# WINGS_SIGNAL_SCH.net
KiCad netlist of a schematic drawn in Altium Designer
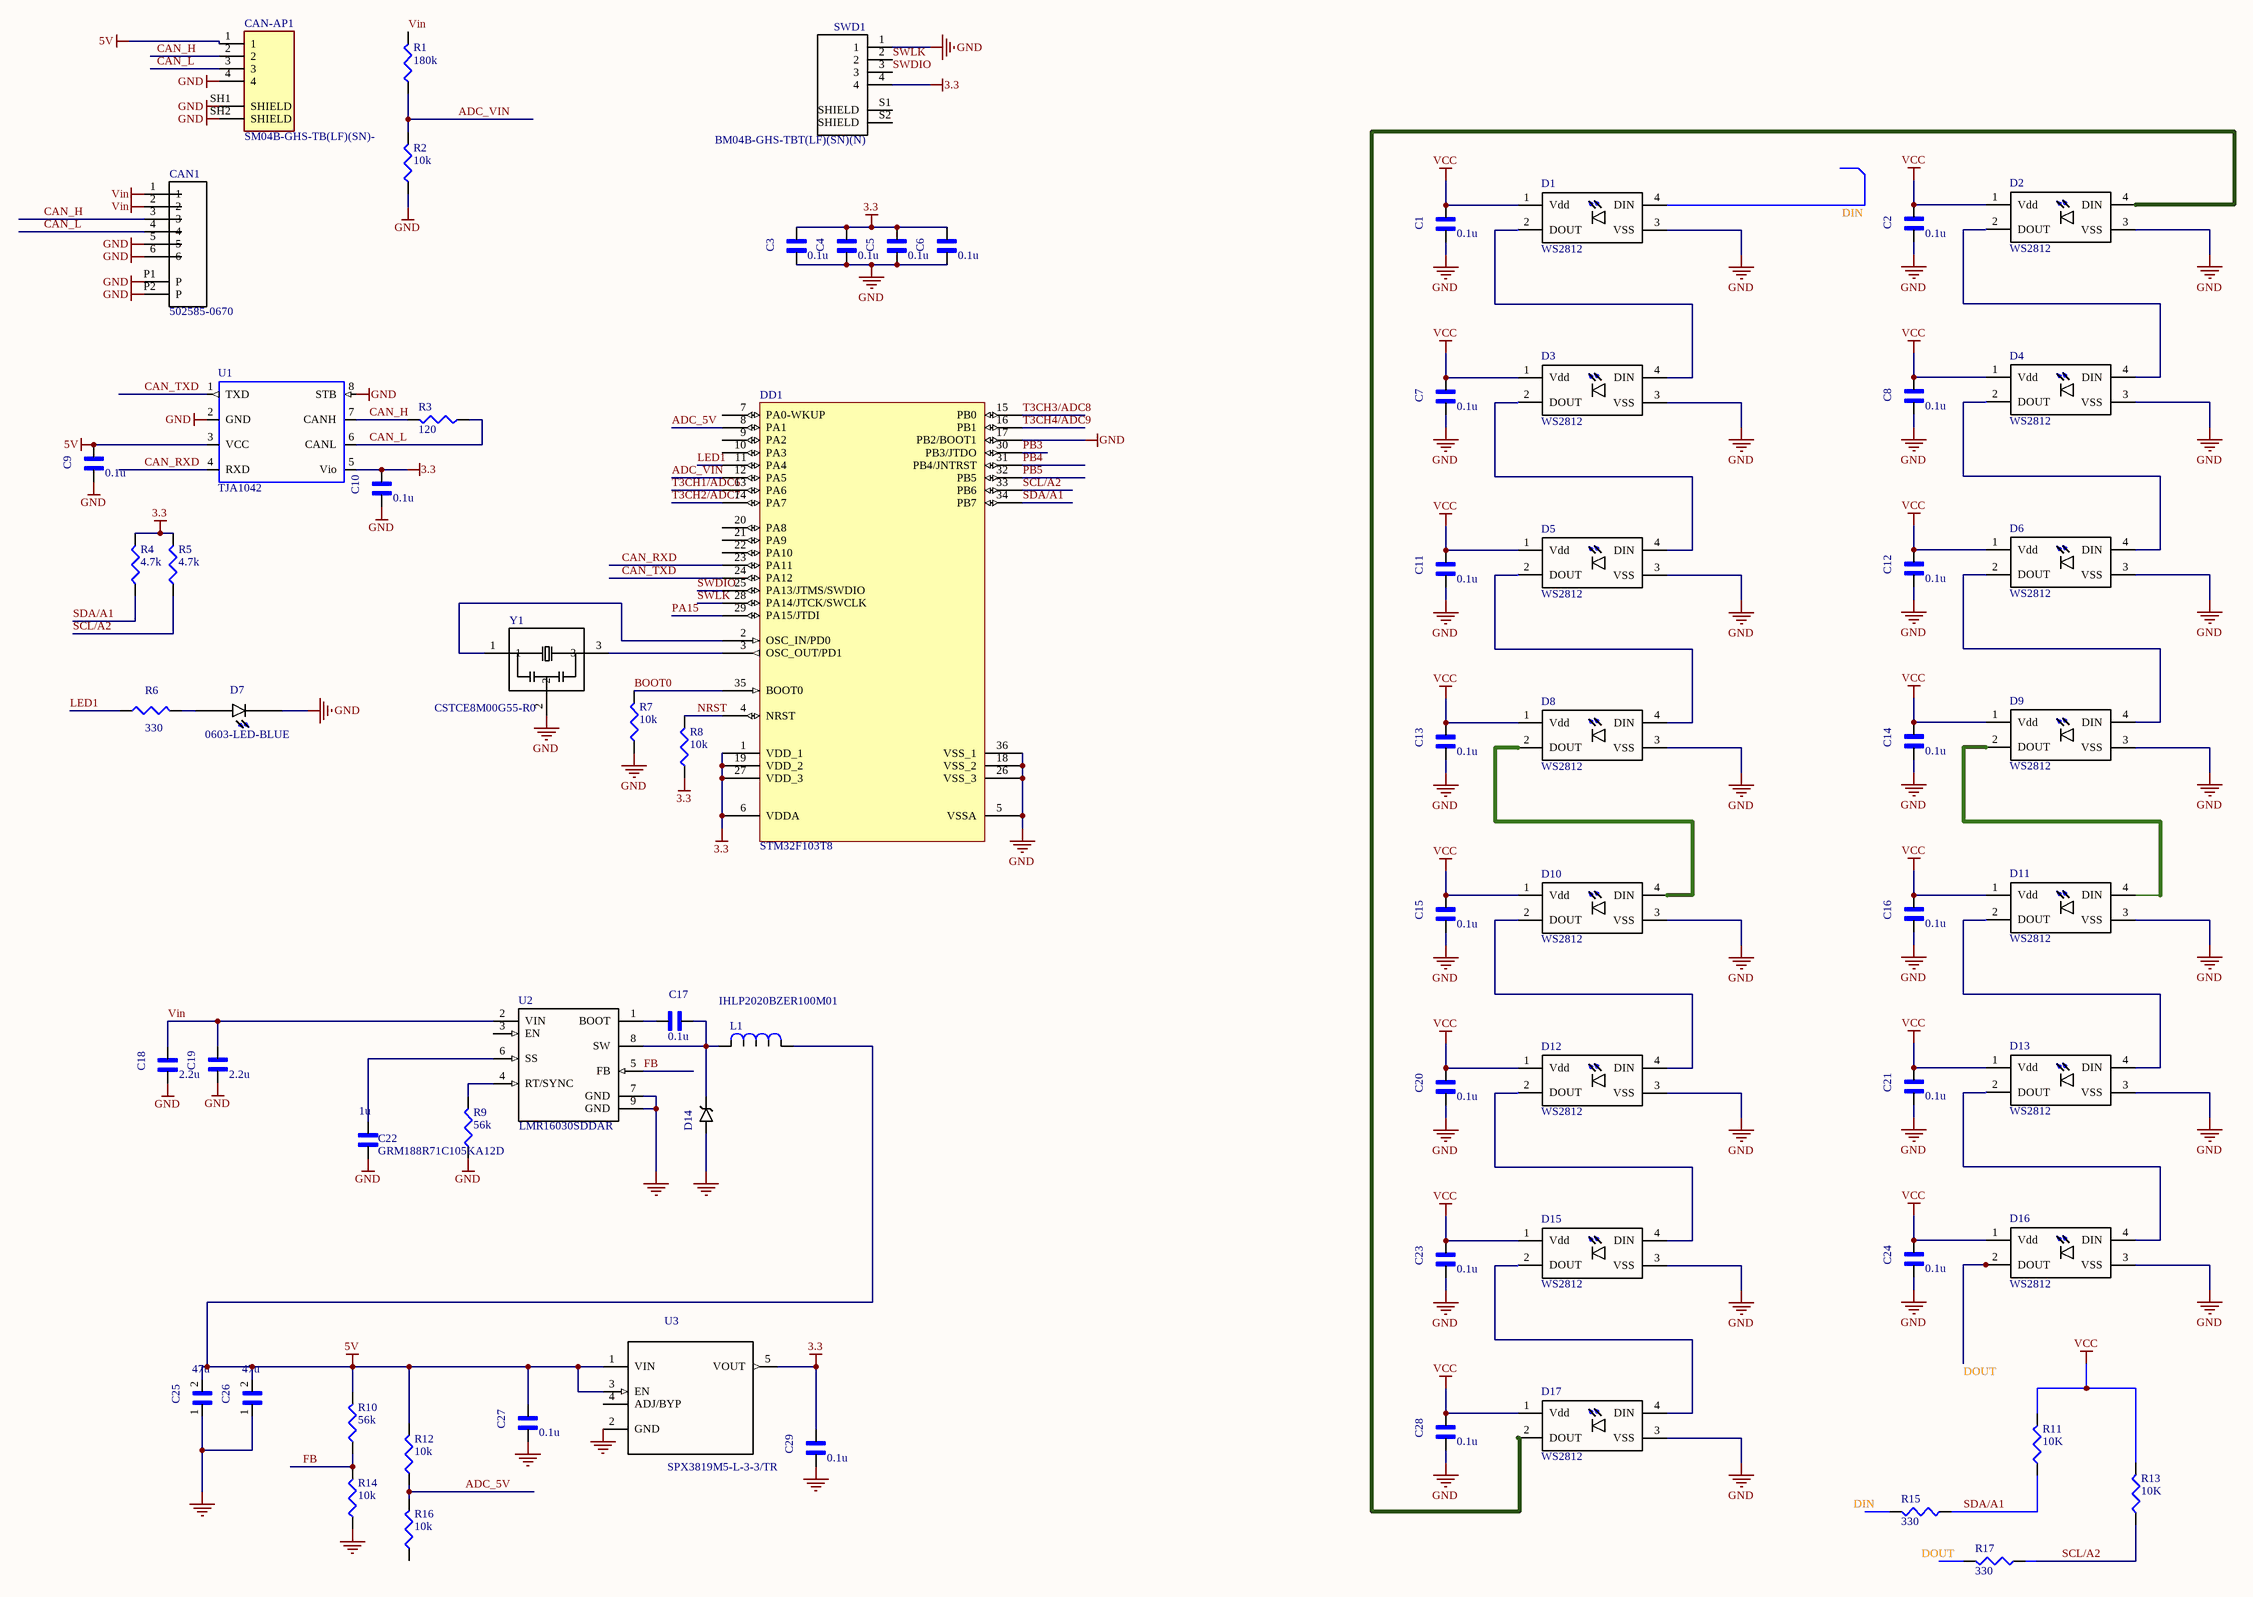
[diagram p0: WINGS_SIGNAL_SCH.SchDoc]

(export (version "E")
  (design (tool "Eeschema 10.0.6"))
  (components
    (comp (ref "C1")
      (value "0.1u")
      (footprint "*CAPC1608X90")
      (description "Cap Thin Film 0.1uf 50v 0603")
      (fields (field (name "MF") "AVX") (field (name "MP") "GX035C104MAT2-500 or CL10B104JB8NNNC"))
      (libsource (lib "lib") (part "GX035C104MAT2-500"))
    )
    (comp (ref "C2")
      (value "0.1u")
      (footprint "*CAPC1608X90")
      (description "Cap Thin Film 0.1uf 50v 0603")
      (fields (field (name "MF") "AVX") (field (name "MP") "GX035C104MAT2-500 or CL10B104JB8NNNC"))
      (libsource (lib "lib") (part "GX035C104MAT2-500"))
    )
    (comp (ref "C3")
      (value "0.1u")
      (footprint "*CAPC1608X90")
      (description "Cap Thin Film 0.1uf 50v 0603")
      (fields (field (name "MF") "AVX") (field (name "MP") "GX035C104MAT2-500 or CL10B104JB8NNNC"))
      (libsource (lib "lib") (part "GX035C104MAT2-500"))
    )
    (comp (ref "C4")
      (value "0.1u")
      (footprint "*CAPC1608X90")
      (description "Cap Thin Film 0.1uf 50v 0603")
      (fields (field (name "MF") "AVX") (field (name "MP") "GX035C104MAT2-500 or CL10B104JB8NNNC"))
      (libsource (lib "lib") (part "GX035C104MAT2-500"))
    )
    (comp (ref "C5")
      (value "0.1u")
      (footprint "*CAPC1608X90")
      (description "Cap Thin Film 0.1uf 50v 0603")
      (fields (field (name "MF") "AVX") (field (name "MP") "GX035C104MAT2-500 or CL10B104JB8NNNC"))
      (libsource (lib "lib") (part "GX035C104MAT2-500"))
    )
    (comp (ref "C6")
      (value "0.1u")
      (footprint "*CAPC1608X90")
      (description "Cap Thin Film 0.1uf 50v 0603")
      (fields (field (name "MF") "AVX") (field (name "MP") "GX035C104MAT2-500 or CL10B104JB8NNNC"))
      (libsource (lib "lib") (part "GX035C104MAT2-500"))
    )
    (comp (ref "C7")
      (value "0.1u")
      (footprint "*CAPC1608X90")
      (description "Cap Thin Film 0.1uf 50v 0603")
      (fields (field (name "MF") "AVX") (field (name "MP") "GX035C104MAT2-500 or CL10B104JB8NNNC"))
      (libsource (lib "lib") (part "GX035C104MAT2-500"))
    )
    (comp (ref "C8")
      (value "0.1u")
      (footprint "*CAPC1608X90")
      (description "Cap Thin Film 0.1uf 50v 0603")
      (fields (field (name "MF") "AVX") (field (name "MP") "GX035C104MAT2-500 or CL10B104JB8NNNC"))
      (libsource (lib "lib") (part "GX035C104MAT2-500"))
    )
    (comp (ref "C9")
      (value "0.1u")
      (footprint "*CAPC1608X90")
      (description "Cap Thin Film 0.1uf 50v 0603")
      (fields (field (name "MF") "AVX") (field (name "MP") "GX035C104MAT2-500 or CL10B104JB8NNNC"))
      (libsource (lib "lib") (part "GX035C104MAT2-500"))
    )
    (comp (ref "C10")
      (value "0.1u")
      (footprint "*CAPC1608X90")
      (description "Cap Thin Film 0.1uf 50v 0603")
      (fields (field (name "MF") "AVX") (field (name "MP") "GX035C104MAT2-500 or CL10B104JB8NNNC"))
      (libsource (lib "lib") (part "GX035C104MAT2-500"))
    )
    (comp (ref "C11")
      (value "0.1u")
      (footprint "*CAPC1608X90")
      (description "Cap Thin Film 0.1uf 50v 0603")
      (fields (field (name "MF") "AVX") (field (name "MP") "GX035C104MAT2-500 or CL10B104JB8NNNC"))
      (libsource (lib "lib") (part "GX035C104MAT2-500"))
    )
    (comp (ref "C12")
      (value "0.1u")
      (footprint "*CAPC1608X90")
      (description "Cap Thin Film 0.1uf 50v 0603")
      (fields (field (name "MF") "AVX") (field (name "MP") "GX035C104MAT2-500 or CL10B104JB8NNNC"))
      (libsource (lib "lib") (part "GX035C104MAT2-500"))
    )
    (comp (ref "C13")
      (value "0.1u")
      (footprint "*CAPC1608X90")
      (description "Cap Thin Film 0.1uf 50v 0603")
      (fields (field (name "MF") "AVX") (field (name "MP") "GX035C104MAT2-500 or CL10B104JB8NNNC"))
      (libsource (lib "lib") (part "GX035C104MAT2-500"))
    )
    (comp (ref "C14")
      (value "0.1u")
      (footprint "*CAPC1608X90")
      (description "Cap Thin Film 0.1uf 50v 0603")
      (fields (field (name "MF") "AVX") (field (name "MP") "GX035C104MAT2-500 or CL10B104JB8NNNC"))
      (libsource (lib "lib") (part "GX035C104MAT2-500"))
    )
    (comp (ref "C15")
      (value "0.1u")
      (footprint "*CAPC1608X90")
      (description "Cap Thin Film 0.1uf 50v 0603")
      (fields (field (name "MF") "AVX") (field (name "MP") "GX035C104MAT2-500 or CL10B104JB8NNNC"))
      (libsource (lib "lib") (part "GX035C104MAT2-500"))
    )
    (comp (ref "C16")
      (value "0.1u")
      (footprint "*CAPC1608X90")
      (description "Cap Thin Film 0.1uf 50v 0603")
      (fields (field (name "MF") "AVX") (field (name "MP") "GX035C104MAT2-500 or CL10B104JB8NNNC"))
      (libsource (lib "lib") (part "GX035C104MAT2-500"))
    )
    (comp (ref "C17")
      (value "0.1u")
      (footprint "*CAPC1608X90")
      (description "Cap Thin Film 0.1uf 50v 0603")
      (fields (field (name "MF") "AVX") (field (name "MP") "GX035C104MAT2-500 or CL10B104JB8NNNC"))
      (libsource (lib "lib") (part "GX035C104MAT2-500"))
    )
    (comp (ref "C18")
      (value "2.2u")
      (footprint "*CAP3216X125N")
      (description "1206 2.2 uF 50 V В±10% Tolerance X7R SMT Multilayer Ceramic Capacitor")
      (fields (field (name "MF") "Murata Electronics") (field (name "MP") "GRM31CR71H225KA88L"))
      (libsource (lib "lib") (part "GRM31CR71H225KA88L"))
    )
    (comp (ref "C19")
      (value "2.2u")
      (footprint "*CAP3216X125N")
      (description "1206 2.2 uF 50 V В±10% Tolerance X7R SMT Multilayer Ceramic Capacitor")
      (fields (field (name "MF") "Murata Electronics") (field (name "MP") "GRM31CR71H225KA88L"))
      (libsource (lib "lib") (part "GRM31CR71H225KA88L"))
    )
    (comp (ref "C20")
      (value "0.1u")
      (footprint "*CAPC1608X90")
      (description "Cap Thin Film 0.1uf 50v 0603")
      (fields (field (name "MF") "AVX") (field (name "MP") "GX035C104MAT2-500 or CL10B104JB8NNNC"))
      (libsource (lib "lib") (part "GX035C104MAT2-500"))
    )
    (comp (ref "C21")
      (value "0.1u")
      (footprint "*CAPC1608X90")
      (description "Cap Thin Film 0.1uf 50v 0603")
      (fields (field (name "MF") "AVX") (field (name "MP") "GX035C104MAT2-500 or CL10B104JB8NNNC"))
      (libsource (lib "lib") (part "GX035C104MAT2-500"))
    )
    (comp (ref "C22")
      (value "GRM188R71C105KA12D")
      (footprint "CAPC1608X90N")
      (description "SMD Capacitor X7R(EIA) with Capacitance: 1.0uF Tol. 10%. Rated Voltage: 16Vdc")
      (fields (field (name "MF") "Murata Electronics") (field (name "ALTIUM_VALUE") "1u"))
      (libsource (lib "lib") (part "GRM188R71C105KA12D"))
    )
    (comp (ref "C23")
      (value "0.1u")
      (footprint "*CAPC1608X90")
      (description "Cap Thin Film 0.1uf 50v 0603")
      (fields (field (name "MF") "AVX") (field (name "MP") "GX035C104MAT2-500 or CL10B104JB8NNNC"))
      (libsource (lib "lib") (part "GX035C104MAT2-500"))
    )
    (comp (ref "C24")
      (value "0.1u")
      (footprint "*CAPC1608X90")
      (description "Cap Thin Film 0.1uf 50v 0603")
      (fields (field (name "MF") "AVX") (field (name "MP") "GX035C104MAT2-500 or CL10B104JB8NNNC"))
      (libsource (lib "lib") (part "GX035C104MAT2-500"))
    )
    (comp (ref "C25")
      (value "47u")
      (footprint "*CAPC3216X125N")
      (description "Multilayer Ceramic Capacitor, GRM Series, 47 - F, - 10%, X5R, 10 V, 1206 [3216 Metric]")
      (fields (field (name "MF") "Murata Electronics") (field (name "MP") "GRM31CR61A476KE15L"))
      (libsource (lib "lib") (part "GRM31CR61A476KE15L"))
    )
    (comp (ref "C26")
      (value "47u")
      (footprint "*CAPC3216X125N")
      (description "Multilayer Ceramic Capacitor, GRM Series, 47 - F, - 10%, X5R, 10 V, 1206 [3216 Metric]")
      (fields (field (name "MF") "Murata Electronics") (field (name "MP") "GRM31CR61A476KE15L"))
      (libsource (lib "lib") (part "GRM31CR61A476KE15L"))
    )
    (comp (ref "C27")
      (value "0.1u")
      (footprint "*CAPC1608X90")
      (description "Cap Thin Film 0.1uf 50v 0603")
      (fields (field (name "MF") "AVX") (field (name "MP") "GX035C104MAT2-500"))
      (libsource (lib "lib") (part "GX035C104MAT2-500"))
    )
    (comp (ref "C28")
      (value "0.1u")
      (footprint "*CAPC1608X90")
      (description "Cap Thin Film 0.1uf 50v 0603")
      (fields (field (name "MF") "AVX") (field (name "MP") "GX035C104MAT2-500 or CL10B104JB8NNNC"))
      (libsource (lib "lib") (part "GX035C104MAT2-500"))
    )
    (comp (ref "C29")
      (value "0.1u")
      (footprint "*CAPC1608X90")
      (description "Cap Thin Film 0.1uf 50v 0603")
      (fields (field (name "MF") "AVX") (field (name "MP") "GX035C104MAT2-500"))
      (libsource (lib "lib") (part "GX035C104MAT2-500"))
    )
    (comp (ref "CAN-AP1")
      (value "SM04B-GHS-TB(LF)(SN)-")
      (footprint "JST_SM04B-GHS-TB(LF)(SN)-")
      (description "Connector Header Surface Mount, Right Angle 4 position 0.049 _1.25mm_")
      (fields (field (name "MP") "SM04B-GHS-TB(LF)(SN)") (field (name "MF") "JST Sales"))
      (libsource (lib "lib") (part "SM04B-GHS-TB(LF)(SN)-"))
    )
    (comp (ref "CAN1")
      (value "502585-0670")
      (footprint "MOLEX_502585-0670")
      (fields (field (name "MF") "Molex"))
      (libsource (lib "lib") (part "502585-0670"))
    )
    (comp (ref "D1")
      (value "WS2812")
      (footprint "LED_WS2812")
      (description "Addressable Lighting - 5 LED Discrete Serial _Shift Register_ Red, Green, Blue _RGB_ 5.00mm Dia")
      (fields (field (name "MF") "SparkFun Electronics"))
      (libsource (lib "lib") (part "WS2812"))
    )
    (comp (ref "D2")
      (value "WS2812")
      (footprint "LED_WS2812")
      (description "Addressable Lighting - 5 LED Discrete Serial _Shift Register_ Red, Green, Blue _RGB_ 5.00mm Dia")
      (fields (field (name "MF") "SparkFun Electronics"))
      (libsource (lib "lib") (part "WS2812"))
    )
    (comp (ref "D3")
      (value "WS2812")
      (footprint "LED_WS2812")
      (description "Addressable Lighting - 5 LED Discrete Serial _Shift Register_ Red, Green, Blue _RGB_ 5.00mm Dia")
      (fields (field (name "MF") "SparkFun Electronics"))
      (libsource (lib "lib") (part "WS2812"))
    )
    (comp (ref "D4")
      (value "WS2812")
      (footprint "LED_WS2812")
      (description "Addressable Lighting - 5 LED Discrete Serial _Shift Register_ Red, Green, Blue _RGB_ 5.00mm Dia")
      (fields (field (name "MF") "SparkFun Electronics"))
      (libsource (lib "lib") (part "WS2812"))
    )
    (comp (ref "D5")
      (value "WS2812")
      (footprint "LED_WS2812")
      (description "Addressable Lighting - 5 LED Discrete Serial _Shift Register_ Red, Green, Blue _RGB_ 5.00mm Dia")
      (fields (field (name "MF") "SparkFun Electronics"))
      (libsource (lib "lib") (part "WS2812"))
    )
    (comp (ref "D6")
      (value "WS2812")
      (footprint "LED_WS2812")
      (description "Addressable Lighting - 5 LED Discrete Serial _Shift Register_ Red, Green, Blue _RGB_ 5.00mm Dia")
      (fields (field (name "MF") "SparkFun Electronics"))
      (libsource (lib "lib") (part "WS2812"))
    )
    (comp (ref "D7")
      (value "0603-LED-BLUE")
      (footprint "*LEDM1608X80_LTE-C1906R-14(Primary)")
      (description "LED IrLED Chip LED 2-Pin SMD T/R")
      (libsource (lib "lib") (part "LTE-C1906R-14"))
    )
    (comp (ref "D8")
      (value "WS2812")
      (footprint "LED_WS2812")
      (description "Addressable Lighting - 5 LED Discrete Serial _Shift Register_ Red, Green, Blue _RGB_ 5.00mm Dia")
      (fields (field (name "MF") "SparkFun Electronics"))
      (libsource (lib "lib") (part "WS2812"))
    )
    (comp (ref "D9")
      (value "WS2812")
      (footprint "LED_WS2812")
      (description "Addressable Lighting - 5 LED Discrete Serial _Shift Register_ Red, Green, Blue _RGB_ 5.00mm Dia")
      (fields (field (name "MF") "SparkFun Electronics"))
      (libsource (lib "lib") (part "WS2812"))
    )
    (comp (ref "D10")
      (value "WS2812")
      (footprint "LED_WS2812")
      (description "Addressable Lighting - 5 LED Discrete Serial _Shift Register_ Red, Green, Blue _RGB_ 5.00mm Dia")
      (fields (field (name "MF") "SparkFun Electronics"))
      (libsource (lib "lib") (part "WS2812"))
    )
    (comp (ref "D11")
      (value "WS2812")
      (footprint "LED_WS2812")
      (description "Addressable Lighting - 5 LED Discrete Serial _Shift Register_ Red, Green, Blue _RGB_ 5.00mm Dia")
      (fields (field (name "MF") "SparkFun Electronics"))
      (libsource (lib "lib") (part "WS2812"))
    )
    (comp (ref "D12")
      (value "WS2812")
      (footprint "LED_WS2812")
      (description "Addressable Lighting - 5 LED Discrete Serial _Shift Register_ Red, Green, Blue _RGB_ 5.00mm Dia")
      (fields (field (name "MF") "SparkFun Electronics"))
      (libsource (lib "lib") (part "WS2812"))
    )
    (comp (ref "D13")
      (value "WS2812")
      (footprint "LED_WS2812")
      (description "Addressable Lighting - 5 LED Discrete Serial _Shift Register_ Red, Green, Blue _RGB_ 5.00mm Dia")
      (fields (field (name "MF") "SparkFun Electronics"))
      (libsource (lib "lib") (part "WS2812"))
    )
    (comp (ref "D14")
      (value "SK56")
      (footprint "*SMB_P6SMB62AT3G(Primary)")
      (description "Диод Шоттки 5А 60В [SMB / DO-214AA]")
      (fields (field (name "MF") "Littelfuse Inc."))
      (libsource (lib "lib") (part "SK56"))
    )
    (comp (ref "D15")
      (value "WS2812")
      (footprint "LED_WS2812")
      (description "Addressable Lighting - 5 LED Discrete Serial _Shift Register_ Red, Green, Blue _RGB_ 5.00mm Dia")
      (fields (field (name "MF") "SparkFun Electronics"))
      (libsource (lib "lib") (part "WS2812"))
    )
    (comp (ref "D16")
      (value "WS2812")
      (footprint "LED_WS2812")
      (description "Addressable Lighting - 5 LED Discrete Serial _Shift Register_ Red, Green, Blue _RGB_ 5.00mm Dia")
      (fields (field (name "MF") "SparkFun Electronics"))
      (libsource (lib "lib") (part "WS2812"))
    )
    (comp (ref "D17")
      (value "WS2812")
      (footprint "LED_WS2812")
      (description "Addressable Lighting - 5 LED Discrete Serial _Shift Register_ Red, Green, Blue _RGB_ 5.00mm Dia")
      (fields (field (name "MF") "SparkFun Electronics"))
      (libsource (lib "lib") (part "WS2812"))
    )
    (comp (ref "DD1")
      (value "STM32F103T8")
      (footprint "*QFN50P600X600X100-37N")
      (description "STM32F103T8U6, Микроконтроллер 32BIT ARM 64K FLASH [VFQFPN-36]")
      (fields (field (name "MF") "STM") (field (name "MP") "STM32F103T8U6"))
      (libsource (lib "lib") (part "STM32F103T8"))
    )
    (comp (ref "L1")
      (value "IHLP2020BZER100M01")
      (footprint "IHLP")
      (description "10ÂµH Shielded Molded Inductor 2.3A 199mOhm Max Nonstandard")
      (fields (field (name "MF") "Vishay Dale"))
      (libsource (lib "lib") (part "IHLP2020BZER100M01"))
    )
    (comp (ref "R1")
      (value "180k")
      (footprint "J1-0603")
      (description "Resistor")
      (fields (field (name "MP") "180K 1% 0603") (field (name "Comment") "Res3"))
      (libsource (lib "Miscellaneous Devices") (part "Res3"))
    )
    (comp (ref "R2")
      (value "10k")
      (footprint "J1-0603")
      (description "Resistor")
      (fields (field (name "MP") "10K 1% 0603") (field (name "Comment") "Res3"))
      (libsource (lib "Miscellaneous Devices") (part "Res3"))
    )
    (comp (ref "R3")
      (value "120")
      (footprint "J1-0603")
      (description "120 Ohms 1 0.1 W 1 10 W Chip Resistor 0603 1608 Metric Thick Film")
      (fields (field (name "MP") "RC0603FR-07120RL") (field (name "Comment") "Res3"))
      (libsource (lib "Miscellaneous Devices") (part "Res3"))
    )
    (comp (ref "R4")
      (value "4.7k")
      (footprint "J1-0603")
      (description "Resistor")
      (fields (field (name "MP") "4.7K 1% 0603") (field (name "Comment") "Res3"))
      (libsource (lib "Miscellaneous Devices") (part "Res3"))
    )
    (comp (ref "R5")
      (value "4.7k")
      (footprint "J1-0603")
      (description "Resistor")
      (fields (field (name "MP") "4.7K 1% 0603") (field (name "Comment") "Res3"))
      (libsource (lib "Miscellaneous Devices") (part "Res3"))
    )
    (comp (ref "R6")
      (value "330")
      (footprint "J1-0603")
      (description "Resistor")
      (fields (field (name "MP") "RC0603FR-07330RL") (field (name "Comment") "Res3"))
      (libsource (lib "Miscellaneous Devices") (part "Res3"))
    )
    (comp (ref "R7")
      (value "10k")
      (footprint "J1-0603")
      (description "10 kOhms 1 0.1 W 1 10 W Chip Resistor 0603 1608 Metric Thick Film")
      (fields (field (name "MF") "Yageo or NXP") (field (name "MP") "10K 1% 0603"))
      (libsource (lib "CAN_NODE_MINI") (part "RC0603FR-0710KL"))
    )
    (comp (ref "R8")
      (value "10k")
      (footprint "J1-0603")
      (description "10 kOhms 1 0.1 W 1 10 W Chip Resistor 0603 1608 Metric Thick Film")
      (fields (field (name "MF") "Yageo or NXP") (field (name "MP") "10K 1% 0603"))
      (libsource (lib "CAN_NODE_MINI") (part "RC0603FR-0710KL"))
    )
    (comp (ref "R9")
      (value "56k")
      (footprint "J1-0603")
      (description "Resistor")
      (fields (field (name "MP") "RC0603FR-0756KL") (field (name "Comment") "Res3"))
      (libsource (lib "Miscellaneous Devices") (part "Res3"))
    )
    (comp (ref "R10")
      (value "56k")
      (footprint "J1-0603")
      (description "Resistor")
      (fields (field (name "MP") "RC0603FR-0756KL") (field (name "Comment") "Res3"))
      (libsource (lib "Miscellaneous Devices") (part "Res3"))
    )
    (comp (ref "R11")
      (value "10K")
      (footprint "J1-0603")
      (description "Resistor")
      (fields (field (name "MP") "4.7K 1% 0603") (field (name "Comment") "Res3"))
      (libsource (lib "Miscellaneous Devices") (part "Res3"))
    )
    (comp (ref "R12")
      (value "10k")
      (footprint "J1-0603")
      (description "10 kOhms 1 0.1 W 1 10 W Chip Resistor 0603 1608 Metric Thick Film")
      (fields (field (name "MF") "Yageo or NXP") (field (name "MP") "10K 1% 0603"))
      (libsource (lib "CAN_NODE_MINI") (part "RC0603FR-0710KL"))
    )
    (comp (ref "R13")
      (value "10K")
      (footprint "J1-0603")
      (description "Resistor")
      (fields (field (name "MP") "4.7K 1% 0603") (field (name "Comment") "Res3"))
      (libsource (lib "Miscellaneous Devices") (part "Res3"))
    )
    (comp (ref "R14")
      (value "10k")
      (footprint "J1-0603")
      (description "10 kOhms 1 0.1 W 1 10 W Chip Resistor 0603 1608 Metric Thick Film")
      (fields (field (name "MF") "Yageo or NXP") (field (name "MP") "10K 1% 0603"))
      (libsource (lib "CAN_NODE_MINI") (part "RC0603FR-0710KL"))
    )
    (comp (ref "R15")
      (value "330")
      (footprint "J1-0603")
      (description "Resistor")
      (fields (field (name "MP") "4.7K 1% 0603") (field (name "Comment") "Res3"))
      (libsource (lib "Miscellaneous Devices") (part "Res3"))
    )
    (comp (ref "R16")
      (value "10k")
      (footprint "J1-0603")
      (description "10 kOhms 1 0.1 W 1 10 W Chip Resistor 0603 1608 Metric Thick Film")
      (fields (field (name "MF") "Yageo or NXP") (field (name "MP") "10K 1% 0603"))
      (libsource (lib "CAN_NODE_MINI") (part "RC0603FR-0710KL"))
    )
    (comp (ref "R17")
      (value "330")
      (footprint "J1-0603")
      (description "Resistor")
      (fields (field (name "MP") "4.7K 1% 0603") (field (name "Comment") "Res3"))
      (libsource (lib "Miscellaneous Devices") (part "Res3"))
    )
    (comp (ref "SWD1")
      (value "BM04B-GHS-TBT(LF)(SN)(N)")
      (footprint "JST_BM04B-GHS-holes")
      (description "Conn Shrouded Header HDR 4 POS 1.25mm Solder ST SMD Reel")
      (fields (field (name "MF") "JST Sales") (field (name "MP") "SM04B-GHS-TB(LF)(SN)"))
      (libsource (lib "lib") (part "BM04B-GHS-TBT(LF)(SN)(N)"))
    )
    (comp (ref "U1")
      (value "TJA1042")
      (footprint "SOT782-1")
      (description "1/1 Transceiver Half CANbus 8-SO")
      (fields (field (name "MF") "NXP USA"))
      (libsource (lib "lib") (part "TJA1042"))
    )
    (comp (ref "U2")
      (value "LMR16030SDDAR")
      (footprint "*SOIC127P600X170-9N - duplicate")
      (fields (field (name "MF") "Texas Instruments"))
      (libsource (lib "lib") (part "LMR16030SDDAR"))
    )
    (comp (ref "U3")
      (value "SPX3819M5-L-3-3/TR")
      (footprint "*SOT95P280X145-5N")
      (description "Low Dropout Voltage Regulator, Adjustable 0.5A, В±1%, 2.5 to 16 Vin, 5-Pin SOT-23")
      (fields (field (name "MF") "MaxLinear, Inc."))
      (libsource (lib "DC_DC") (part "SPX3819M5-L"))
    )
    (comp (ref "Y1")
      (value "CSTCE8M00G55-R0")
      (footprint "*OSC_CSTCE8M00G55-R0")
      (description "Ceramic Resonator 8MHz ??0.5% _Tol_ ??0.2% _Stability_ 33pF 40Ohm 3-Pin CSMD T/R")
      (fields (field (name "MF") "Murata"))
      (libsource (lib "DC_DC") (part "CSTCE8M00G55-R0"))
    )
  )
  (nets
    (net (code "1") (name "/ADC_5V") (class "Default")
      (node (ref "DD1") (pin "8") (pinfunction "PA1_8") (pintype "bidirectional"))
      (node (ref "R12") (pin "1") (pinfunction "1_1") (pintype "passive"))
      (node (ref "R16") (pin "2") (pinfunction "2_2") (pintype "passive"))
    )
    (net (code "2") (name "/ADC_VIN") (class "Default")
      (node (ref "DD1") (pin "12") (pinfunction "PA5_12") (pintype "bidirectional"))
      (node (ref "R1") (pin "1") (pinfunction "1_1") (pintype "passive"))
      (node (ref "R2") (pin "2") (pinfunction "2_2") (pintype "passive"))
    )
    (net (code "3") (name "/BOOT0") (class "Default")
      (node (ref "DD1") (pin "35") (pinfunction "BOOT0_35") (pintype "input"))
      (node (ref "R7") (pin "2") (pinfunction "2_2") (pintype "passive"))
    )
    (net (code "4") (name "/CAN_H") (class "Default")
      (node (ref "CAN-AP1") (pin "2") (pinfunction "2_2") (pintype "passive"))
      (node (ref "CAN1") (pin "3") (pinfunction "3_3") (pintype "passive"))
      (node (ref "R3") (pin "2") (pinfunction "2_2") (pintype "passive"))
      (node (ref "U1") (pin "7") (pinfunction "CANH_7") (pintype "bidirectional"))
    )
    (net (code "5") (name "/CAN_L") (class "Default")
      (node (ref "CAN-AP1") (pin "3") (pinfunction "3_3") (pintype "passive"))
      (node (ref "CAN1") (pin "4") (pinfunction "4_4") (pintype "passive"))
      (node (ref "R3") (pin "1") (pinfunction "1_1") (pintype "passive"))
      (node (ref "U1") (pin "6") (pinfunction "CANL_6") (pintype "bidirectional"))
    )
    (net (code "6") (name "/CAN_RXD") (class "Default")
      (node (ref "DD1") (pin "23") (pinfunction "PA11_23") (pintype "bidirectional"))
      (node (ref "U1") (pin "4") (pinfunction "RXD_4") (pintype "bidirectional"))
    )
    (net (code "7") (name "/CAN_TXD") (class "Default")
      (node (ref "DD1") (pin "24") (pinfunction "PA12_24") (pintype "bidirectional"))
      (node (ref "U1") (pin "1") (pinfunction "TXD_1") (pintype "output"))
    )
    (net (code "8") (name "/DIN") (class "Default")
      (node (ref "D1") (pin "4") (pinfunction "DIN_4") (pintype "power_in"))
      (node (ref "R15") (pin "2") (pinfunction "2_2") (pintype "passive"))
    )
    (net (code "9") (name "/DOUT") (class "Default")
      (node (ref "D16") (pin "2") (pinfunction "DOUT_2") (pintype "power_in"))
      (node (ref "R17") (pin "2") (pinfunction "2_2") (pintype "passive"))
    )
    (net (code "10") (name "/FB") (class "Default")
      (node (ref "R10") (pin "1") (pinfunction "1_1") (pintype "passive"))
      (node (ref "R14") (pin "2") (pinfunction "2_2") (pintype "passive"))
      (node (ref "U2") (pin "5") (pinfunction "FB_5") (pintype "input"))
    )
    (net (code "11") (name "/LED1") (class "Default")
      (node (ref "DD1") (pin "11") (pinfunction "PA4_11") (pintype "bidirectional"))
      (node (ref "R6") (pin "1") (pinfunction "1_1") (pintype "passive"))
    )
    (net (code "12") (name "/NRST") (class "Default")
      (node (ref "DD1") (pin "4") (pinfunction "NRST_4") (pintype "bidirectional"))
      (node (ref "R8") (pin "2") (pinfunction "2_2") (pintype "passive"))
    )
    (net (code "13") (name "/PA15") (class "Default")
      (node (ref "DD1") (pin "29") (pinfunction "PA15/JTDI_29") (pintype "bidirectional"))
    )
    (net (code "14") (name "/PB3") (class "Default")
      (node (ref "DD1") (pin "30") (pinfunction "PB3/JTDO_30") (pintype "bidirectional"))
    )
    (net (code "15") (name "/PB4") (class "Default")
      (node (ref "DD1") (pin "31") (pinfunction "PB4/JNTRST_31") (pintype "bidirectional"))
    )
    (net (code "16") (name "/PB5") (class "Default")
      (node (ref "DD1") (pin "32") (pinfunction "PB5_32") (pintype "bidirectional"))
    )
    (net (code "17") (name "/SCL{slash}A2") (class "Default")
      (node (ref "DD1") (pin "33") (pinfunction "PB6_33") (pintype "bidirectional"))
      (node (ref "R13") (pin "1") (pinfunction "1_1") (pintype "passive"))
      (node (ref "R17") (pin "1") (pinfunction "1_1") (pintype "passive"))
      (node (ref "R5") (pin "1") (pinfunction "1_1") (pintype "passive"))
    )
    (net (code "18") (name "/SDA{slash}A1") (class "Default")
      (node (ref "DD1") (pin "34") (pinfunction "PB7_34") (pintype "bidirectional"))
      (node (ref "R11") (pin "1") (pinfunction "1_1") (pintype "passive"))
      (node (ref "R15") (pin "1") (pinfunction "1_1") (pintype "passive"))
      (node (ref "R4") (pin "1") (pinfunction "1_1") (pintype "passive"))
    )
    (net (code "19") (name "/SWDIO") (class "Default")
      (node (ref "DD1") (pin "25") (pinfunction "PA13/JTMS/SWDIO_25") (pintype "bidirectional"))
      (node (ref "SWD1") (pin "3") (pinfunction "3_3") (pintype "passive"))
    )
    (net (code "20") (name "/SWLK") (class "Default")
      (node (ref "DD1") (pin "28") (pinfunction "PA14/JTCK/SWCLK_28") (pintype "bidirectional"))
      (node (ref "SWD1") (pin "2") (pinfunction "2_2") (pintype "passive"))
    )
    (net (code "21") (name "/T3CH1{slash}ADC6") (class "Default")
      (node (ref "DD1") (pin "13") (pinfunction "PA6_13") (pintype "bidirectional"))
    )
    (net (code "22") (name "/T3CH2{slash}ADC7") (class "Default")
      (node (ref "DD1") (pin "14") (pinfunction "PA7_14") (pintype "bidirectional"))
    )
    (net (code "23") (name "/T3CH3{slash}ADC8") (class "Default")
      (node (ref "DD1") (pin "15") (pinfunction "PB0_15") (pintype "bidirectional"))
    )
    (net (code "24") (name "/T3CH4{slash}ADC9") (class "Default")
      (node (ref "DD1") (pin "16") (pinfunction "PB1_16") (pintype "bidirectional"))
    )
    (net (code "25") (name "3.3") (class "Default")
      (node (ref "C10") (pin "1") (pinfunction "1_1") (pintype "passive"))
      (node (ref "C29") (pin "1") (pinfunction "1_1") (pintype "passive"))
      (node (ref "C3") (pin "1") (pinfunction "1_1") (pintype "passive"))
      (node (ref "C4") (pin "1") (pinfunction "1_1") (pintype "passive"))
      (node (ref "C5") (pin "1") (pinfunction "1_1") (pintype "passive"))
      (node (ref "C6") (pin "1") (pinfunction "1_1") (pintype "passive"))
      (node (ref "DD1") (pin "1") (pinfunction "VDD_1_1") (pintype "power_in"))
      (node (ref "DD1") (pin "19") (pinfunction "VDD_2_19") (pintype "power_in"))
      (node (ref "DD1") (pin "27") (pinfunction "VDD_3_27") (pintype "power_in"))
      (node (ref "DD1") (pin "6") (pinfunction "VDDA_6") (pintype "power_in"))
      (node (ref "R4") (pin "2") (pinfunction "2_2") (pintype "passive"))
      (node (ref "R5") (pin "2") (pinfunction "2_2") (pintype "passive"))
      (node (ref "R8") (pin "1") (pinfunction "1_1") (pintype "passive"))
      (node (ref "SWD1") (pin "4") (pinfunction "4_4") (pintype "passive"))
      (node (ref "U1") (pin "5") (pinfunction "Vio_5") (pintype "power_in"))
      (node (ref "U3") (pin "5") (pinfunction "VOUT_5") (pintype "output"))
    )
    (net (code "26") (name "5V") (class "Default")
      (node (ref "C25") (pin "2") (pinfunction "2_2") (pintype "passive"))
      (node (ref "C26") (pin "2") (pinfunction "2_2") (pintype "passive"))
      (node (ref "C27") (pin "1") (pinfunction "1_1") (pintype "passive"))
      (node (ref "C9") (pin "1") (pinfunction "1_1") (pintype "passive"))
      (node (ref "CAN-AP1") (pin "1") (pinfunction "1_1") (pintype "passive"))
      (node (ref "L1") (pin "1") (pinfunction "1_1") (pintype "passive"))
      (node (ref "R10") (pin "2") (pinfunction "2_2") (pintype "passive"))
      (node (ref "R12") (pin "2") (pinfunction "2_2") (pintype "passive"))
      (node (ref "U1") (pin "3") (pinfunction "VCC_3") (pintype "power_in"))
      (node (ref "U3") (pin "1") (pinfunction "VIN_1") (pintype "power_in"))
      (node (ref "U3") (pin "3") (pinfunction "EN_3") (pintype "input"))
    )
    (net (code "27") (name "GND") (class "Default")
      (node (ref "C1") (pin "2") (pinfunction "2_2") (pintype "passive"))
      (node (ref "C10") (pin "2") (pinfunction "2_2") (pintype "passive"))
      (node (ref "C11") (pin "2") (pinfunction "2_2") (pintype "passive"))
      (node (ref "C12") (pin "2") (pinfunction "2_2") (pintype "passive"))
      (node (ref "C13") (pin "2") (pinfunction "2_2") (pintype "passive"))
      (node (ref "C14") (pin "2") (pinfunction "2_2") (pintype "passive"))
      (node (ref "C15") (pin "2") (pinfunction "2_2") (pintype "passive"))
      (node (ref "C16") (pin "2") (pinfunction "2_2") (pintype "passive"))
      (node (ref "C18") (pin "2") (pinfunction "2_2") (pintype "passive"))
      (node (ref "C19") (pin "2") (pinfunction "2_2") (pintype "passive"))
      (node (ref "C2") (pin "2") (pinfunction "2_2") (pintype "passive"))
      (node (ref "C20") (pin "2") (pinfunction "2_2") (pintype "passive"))
      (node (ref "C21") (pin "2") (pinfunction "2_2") (pintype "passive"))
      (node (ref "C22") (pin "1") (pinfunction "1_1") (pintype "passive"))
      (node (ref "C23") (pin "2") (pinfunction "2_2") (pintype "passive"))
      (node (ref "C24") (pin "2") (pinfunction "2_2") (pintype "passive"))
      (node (ref "C25") (pin "1") (pinfunction "1_1") (pintype "passive"))
      (node (ref "C26") (pin "1") (pinfunction "1_1") (pintype "passive"))
      (node (ref "C27") (pin "2") (pinfunction "2_2") (pintype "passive"))
      (node (ref "C28") (pin "2") (pinfunction "2_2") (pintype "passive"))
      (node (ref "C29") (pin "2") (pinfunction "2_2") (pintype "passive"))
      (node (ref "C3") (pin "2") (pinfunction "2_2") (pintype "passive"))
      (node (ref "C4") (pin "2") (pinfunction "2_2") (pintype "passive"))
      (node (ref "C5") (pin "2") (pinfunction "2_2") (pintype "passive"))
      (node (ref "C6") (pin "2") (pinfunction "2_2") (pintype "passive"))
      (node (ref "C7") (pin "2") (pinfunction "2_2") (pintype "passive"))
      (node (ref "C8") (pin "2") (pinfunction "2_2") (pintype "passive"))
      (node (ref "C9") (pin "2") (pinfunction "2_2") (pintype "passive"))
      (node (ref "CAN-AP1") (pin "4") (pinfunction "4_4") (pintype "passive"))
      (node (ref "CAN-AP1") (pin "SH1") (pinfunction "SHIELD_SH1") (pintype "power_in"))
      (node (ref "CAN-AP1") (pin "SH2") (pinfunction "SHIELD_SH2") (pintype "power_in"))
      (node (ref "CAN1") (pin "5") (pinfunction "5_5") (pintype "passive"))
      (node (ref "CAN1") (pin "6") (pinfunction "6_6") (pintype "passive"))
      (node (ref "CAN1") (pin "P1") (pinfunction "P_P1") (pintype "passive"))
      (node (ref "CAN1") (pin "P2") (pinfunction "P_P2") (pintype "passive"))
      (node (ref "D1") (pin "3") (pinfunction "VSS_3") (pintype "power_in"))
      (node (ref "D10") (pin "3") (pinfunction "VSS_3") (pintype "power_in"))
      (node (ref "D11") (pin "3") (pinfunction "VSS_3") (pintype "power_in"))
      (node (ref "D12") (pin "3") (pinfunction "VSS_3") (pintype "power_in"))
      (node (ref "D13") (pin "3") (pinfunction "VSS_3") (pintype "power_in"))
      (node (ref "D14") (pin "A") (pinfunction "A_A") (pintype "power_in"))
      (node (ref "D15") (pin "3") (pinfunction "VSS_3") (pintype "power_in"))
      (node (ref "D16") (pin "3") (pinfunction "VSS_3") (pintype "power_in"))
      (node (ref "D17") (pin "3") (pinfunction "VSS_3") (pintype "power_in"))
      (node (ref "D2") (pin "3") (pinfunction "VSS_3") (pintype "power_in"))
      (node (ref "D3") (pin "3") (pinfunction "VSS_3") (pintype "power_in"))
      (node (ref "D4") (pin "3") (pinfunction "VSS_3") (pintype "power_in"))
      (node (ref "D5") (pin "3") (pinfunction "VSS_3") (pintype "power_in"))
      (node (ref "D6") (pin "3") (pinfunction "VSS_3") (pintype "power_in"))
      (node (ref "D7") (pin "C") (pinfunction "C_C") (pintype "passive"))
      (node (ref "D8") (pin "3") (pinfunction "VSS_3") (pintype "power_in"))
      (node (ref "D9") (pin "3") (pinfunction "VSS_3") (pintype "power_in"))
      (node (ref "DD1") (pin "17") (pinfunction "PB2/BOOT1_17") (pintype "bidirectional"))
      (node (ref "DD1") (pin "18") (pinfunction "VSS_2_18") (pintype "power_in"))
      (node (ref "DD1") (pin "26") (pinfunction "VSS_3_26") (pintype "power_in"))
      (node (ref "DD1") (pin "36") (pinfunction "VSS_1_36") (pintype "power_in"))
      (node (ref "DD1") (pin "5") (pinfunction "VSSA_5") (pintype "power_in"))
      (node (ref "R14") (pin "1") (pinfunction "1_1") (pintype "passive"))
      (node (ref "R2") (pin "1") (pinfunction "1_1") (pintype "passive"))
      (node (ref "R7") (pin "1") (pinfunction "1_1") (pintype "passive"))
      (node (ref "R9") (pin "1") (pinfunction "1_1") (pintype "passive"))
      (node (ref "SWD1") (pin "1") (pinfunction "1_1") (pintype "passive"))
      (node (ref "U1") (pin "2") (pinfunction "GND_2") (pintype "power_in"))
      (node (ref "U1") (pin "8") (pinfunction "STB_8") (pintype "input"))
      (node (ref "U2") (pin "7") (pinfunction "GND_7") (pintype "power_in"))
      (node (ref "U2") (pin "9") (pinfunction "GND_9") (pintype "power_in"))
      (node (ref "U3") (pin "2") (pinfunction "GND_2") (pintype "passive"))
      (node (ref "Y1") (pin "2") (pinfunction "2_2") (pintype "power_in"))
    )
    (net (code "28") (name "Net-(D1-DOUT)") (class "Default")
      (node (ref "D1") (pin "2") (pinfunction "DOUT_2") (pintype "power_in"))
      (node (ref "D3") (pin "4") (pinfunction "DIN_4") (pintype "power_in"))
    )
    (net (code "29") (name "Net-(D2-DOUT)") (class "Default")
      (node (ref "D2") (pin "2") (pinfunction "DOUT_2") (pintype "power_in"))
      (node (ref "D4") (pin "4") (pinfunction "DIN_4") (pintype "power_in"))
    )
    (net (code "30") (name "Net-(D3-DOUT)") (class "Default")
      (node (ref "D3") (pin "2") (pinfunction "DOUT_2") (pintype "power_in"))
      (node (ref "D5") (pin "4") (pinfunction "DIN_4") (pintype "power_in"))
    )
    (net (code "31") (name "Net-(D4-DOUT)") (class "Default")
      (node (ref "D4") (pin "2") (pinfunction "DOUT_2") (pintype "power_in"))
      (node (ref "D6") (pin "4") (pinfunction "DIN_4") (pintype "power_in"))
    )
    (net (code "32") (name "Net-(D5-DOUT)") (class "Default")
      (node (ref "D5") (pin "2") (pinfunction "DOUT_2") (pintype "power_in"))
      (node (ref "D8") (pin "4") (pinfunction "DIN_4") (pintype "power_in"))
    )
    (net (code "33") (name "Net-(D6-DOUT)") (class "Default")
      (node (ref "D6") (pin "2") (pinfunction "DOUT_2") (pintype "power_in"))
      (node (ref "D9") (pin "4") (pinfunction "DIN_4") (pintype "power_in"))
    )
    (net (code "34") (name "Net-(D7-PadA)") (class "Default")
      (node (ref "D7") (pin "A") (pinfunction "A_A") (pintype "passive"))
      (node (ref "R6") (pin "2") (pinfunction "2_2") (pintype "passive"))
    )
    (net (code "35") (name "Net-(D10-DIN)") (class "Default")
      (node (ref "D10") (pin "4") (pinfunction "DIN_4") (pintype "power_in"))
      (node (ref "D8") (pin "2") (pinfunction "DOUT_2") (pintype "power_in"))
    )
    (net (code "36") (name "Net-(D10-DOUT)") (class "Default")
      (node (ref "D10") (pin "2") (pinfunction "DOUT_2") (pintype "power_in"))
      (node (ref "D12") (pin "4") (pinfunction "DIN_4") (pintype "power_in"))
    )
    (net (code "37") (name "Net-(D11-DIN)") (class "Default")
      (node (ref "D11") (pin "4") (pinfunction "DIN_4") (pintype "power_in"))
      (node (ref "D9") (pin "2") (pinfunction "DOUT_2") (pintype "power_in"))
    )
    (net (code "38") (name "Net-(D11-DOUT)") (class "Default")
      (node (ref "D11") (pin "2") (pinfunction "DOUT_2") (pintype "power_in"))
      (node (ref "D13") (pin "4") (pinfunction "DIN_4") (pintype "power_in"))
    )
    (net (code "39") (name "Net-(D12-DOUT)") (class "Default")
      (node (ref "D12") (pin "2") (pinfunction "DOUT_2") (pintype "power_in"))
      (node (ref "D15") (pin "4") (pinfunction "DIN_4") (pintype "power_in"))
    )
    (net (code "40") (name "Net-(D13-DOUT)") (class "Default")
      (node (ref "D13") (pin "2") (pinfunction "DOUT_2") (pintype "power_in"))
      (node (ref "D16") (pin "4") (pinfunction "DIN_4") (pintype "power_in"))
    )
    (net (code "41") (name "Net-(D15-DOUT)") (class "Default")
      (node (ref "D15") (pin "2") (pinfunction "DOUT_2") (pintype "power_in"))
      (node (ref "D17") (pin "4") (pinfunction "DIN_4") (pintype "power_in"))
    )
    (net (code "42") (name "Net-(D17-DOUT)") (class "Default")
      (node (ref "D17") (pin "2") (pinfunction "DOUT_2") (pintype "power_in"))
      (node (ref "D2") (pin "4") (pinfunction "DIN_4") (pintype "power_in"))
    )
    (net (code "43") (name "Net-(DD1-OSC_IN{slash}PD0)") (class "Default")
      (node (ref "DD1") (pin "2") (pinfunction "OSC_IN/PD0_2") (pintype "input"))
      (node (ref "Y1") (pin "1") (pinfunction "1_1") (pintype "passive"))
    )
    (net (code "44") (name "Net-(DD1-OSC_OUT{slash}PD1)") (class "Default")
      (node (ref "DD1") (pin "3") (pinfunction "OSC_OUT/PD1_3") (pintype "output"))
      (node (ref "Y1") (pin "3") (pinfunction "3_3") (pintype "passive"))
    )
    (net (code "45") (name "Net-(U2-BOOT)") (class "Default")
      (node (ref "C17") (pin "2") (pinfunction "2_2") (pintype "passive"))
      (node (ref "U2") (pin "1") (pinfunction "BOOT_1") (pintype "power_in"))
    )
    (net (code "46") (name "Net-(U2-RT{slash}SYNC)") (class "Default")
      (node (ref "R9") (pin "2") (pinfunction "2_2") (pintype "passive"))
      (node (ref "U2") (pin "4") (pinfunction "RT/SYNC_4") (pintype "input"))
    )
    (net (code "47") (name "Net-(U2-SS)") (class "Default")
      (node (ref "C22") (pin "2") (pinfunction "2_2") (pintype "passive"))
      (node (ref "U2") (pin "6") (pinfunction "SS_6") (pintype "input"))
    )
    (net (code "48") (name "Net-(U2-SW)") (class "Default")
      (node (ref "C17") (pin "1") (pinfunction "1_1") (pintype "passive"))
      (node (ref "D14") (pin "C") (pinfunction "C_C") (pintype "power_in"))
      (node (ref "L1") (pin "2") (pinfunction "2_2") (pintype "passive"))
      (node (ref "U2") (pin "8") (pinfunction "SW_8") (pintype "power_in"))
    )
    (net (code "49") (name "VCC") (class "Default")
      (node (ref "C1") (pin "1") (pinfunction "1_1") (pintype "passive"))
      (node (ref "C11") (pin "1") (pinfunction "1_1") (pintype "passive"))
      (node (ref "C12") (pin "1") (pinfunction "1_1") (pintype "passive"))
      (node (ref "C13") (pin "1") (pinfunction "1_1") (pintype "passive"))
      (node (ref "C14") (pin "1") (pinfunction "1_1") (pintype "passive"))
      (node (ref "C15") (pin "1") (pinfunction "1_1") (pintype "passive"))
      (node (ref "C16") (pin "1") (pinfunction "1_1") (pintype "passive"))
      (node (ref "C2") (pin "1") (pinfunction "1_1") (pintype "passive"))
      (node (ref "C20") (pin "1") (pinfunction "1_1") (pintype "passive"))
      (node (ref "C21") (pin "1") (pinfunction "1_1") (pintype "passive"))
      (node (ref "C23") (pin "1") (pinfunction "1_1") (pintype "passive"))
      (node (ref "C24") (pin "1") (pinfunction "1_1") (pintype "passive"))
      (node (ref "C28") (pin "1") (pinfunction "1_1") (pintype "passive"))
      (node (ref "C7") (pin "1") (pinfunction "1_1") (pintype "passive"))
      (node (ref "C8") (pin "1") (pinfunction "1_1") (pintype "passive"))
      (node (ref "D1") (pin "1") (pinfunction "Vdd_1") (pintype "power_in"))
      (node (ref "D10") (pin "1") (pinfunction "Vdd_1") (pintype "power_in"))
      (node (ref "D11") (pin "1") (pinfunction "Vdd_1") (pintype "power_in"))
      (node (ref "D12") (pin "1") (pinfunction "Vdd_1") (pintype "power_in"))
      (node (ref "D13") (pin "1") (pinfunction "Vdd_1") (pintype "power_in"))
      (node (ref "D15") (pin "1") (pinfunction "Vdd_1") (pintype "power_in"))
      (node (ref "D16") (pin "1") (pinfunction "Vdd_1") (pintype "power_in"))
      (node (ref "D17") (pin "1") (pinfunction "Vdd_1") (pintype "power_in"))
      (node (ref "D2") (pin "1") (pinfunction "Vdd_1") (pintype "power_in"))
      (node (ref "D3") (pin "1") (pinfunction "Vdd_1") (pintype "power_in"))
      (node (ref "D4") (pin "1") (pinfunction "Vdd_1") (pintype "power_in"))
      (node (ref "D5") (pin "1") (pinfunction "Vdd_1") (pintype "power_in"))
      (node (ref "D6") (pin "1") (pinfunction "Vdd_1") (pintype "power_in"))
      (node (ref "D8") (pin "1") (pinfunction "Vdd_1") (pintype "power_in"))
      (node (ref "D9") (pin "1") (pinfunction "Vdd_1") (pintype "power_in"))
      (node (ref "R11") (pin "2") (pinfunction "2_2") (pintype "passive"))
      (node (ref "R13") (pin "2") (pinfunction "2_2") (pintype "passive"))
    )
    (net (code "50") (name "Vin") (class "Default")
      (node (ref "C18") (pin "1") (pinfunction "1_1") (pintype "passive"))
      (node (ref "C19") (pin "1") (pinfunction "1_1") (pintype "passive"))
      (node (ref "CAN1") (pin "1") (pinfunction "1_1") (pintype "passive"))
      (node (ref "CAN1") (pin "2") (pinfunction "2_2") (pintype "passive"))
      (node (ref "R1") (pin "2") (pinfunction "2_2") (pintype "passive"))
      (node (ref "U2") (pin "2") (pinfunction "VIN_2") (pintype "power_in"))
    )
    (net (code "51") (name "unconnected-(DD1-PA0-WKUP-Pad7)") (class "Default")
      (node (ref "DD1") (pin "7") (pinfunction "PA0-WKUP_7") (pintype "bidirectional"))
    )
    (net (code "52") (name "unconnected-(DD1-PA2-Pad9)") (class "Default")
      (node (ref "DD1") (pin "9") (pinfunction "PA2_9") (pintype "bidirectional"))
    )
    (net (code "53") (name "unconnected-(DD1-PA3-Pad10)") (class "Default")
      (node (ref "DD1") (pin "10") (pinfunction "PA3_10") (pintype "bidirectional"))
    )
    (net (code "54") (name "unconnected-(DD1-PA8-Pad20)") (class "Default")
      (node (ref "DD1") (pin "20") (pinfunction "PA8_20") (pintype "bidirectional"))
    )
    (net (code "55") (name "unconnected-(DD1-PA9-Pad21)") (class "Default")
      (node (ref "DD1") (pin "21") (pinfunction "PA9_21") (pintype "bidirectional"))
    )
    (net (code "56") (name "unconnected-(DD1-PA10-Pad22)") (class "Default")
      (node (ref "DD1") (pin "22") (pinfunction "PA10_22") (pintype "bidirectional"))
    )
    (net (code "57") (name "unconnected-(R16-Pad1)") (class "Default")
      (node (ref "R16") (pin "1") (pinfunction "1_1") (pintype "passive"))
    )
    (net (code "58") (name "unconnected-(SWD1-SHIELD-PadS1)") (class "Default")
      (node (ref "SWD1") (pin "S1") (pinfunction "SHIELD_S1") (pintype "passive"))
    )
    (net (code "59") (name "unconnected-(SWD1-SHIELD-PadS2)") (class "Default")
      (node (ref "SWD1") (pin "S2") (pinfunction "SHIELD_S2") (pintype "passive"))
    )
    (net (code "60") (name "unconnected-(U2-EN-Pad3)") (class "Default")
      (node (ref "U2") (pin "3") (pinfunction "EN_3") (pintype "input"))
    )
    (net (code "61") (name "unconnected-(U3-ADJ{slash}BYP-Pad4)") (class "Default")
      (node (ref "U3") (pin "4") (pinfunction "ADJ/BYP_4") (pintype "passive"))
    )
  )
)
